# Power.net
KiCad netlist of a schematic drawn in Altium Designer
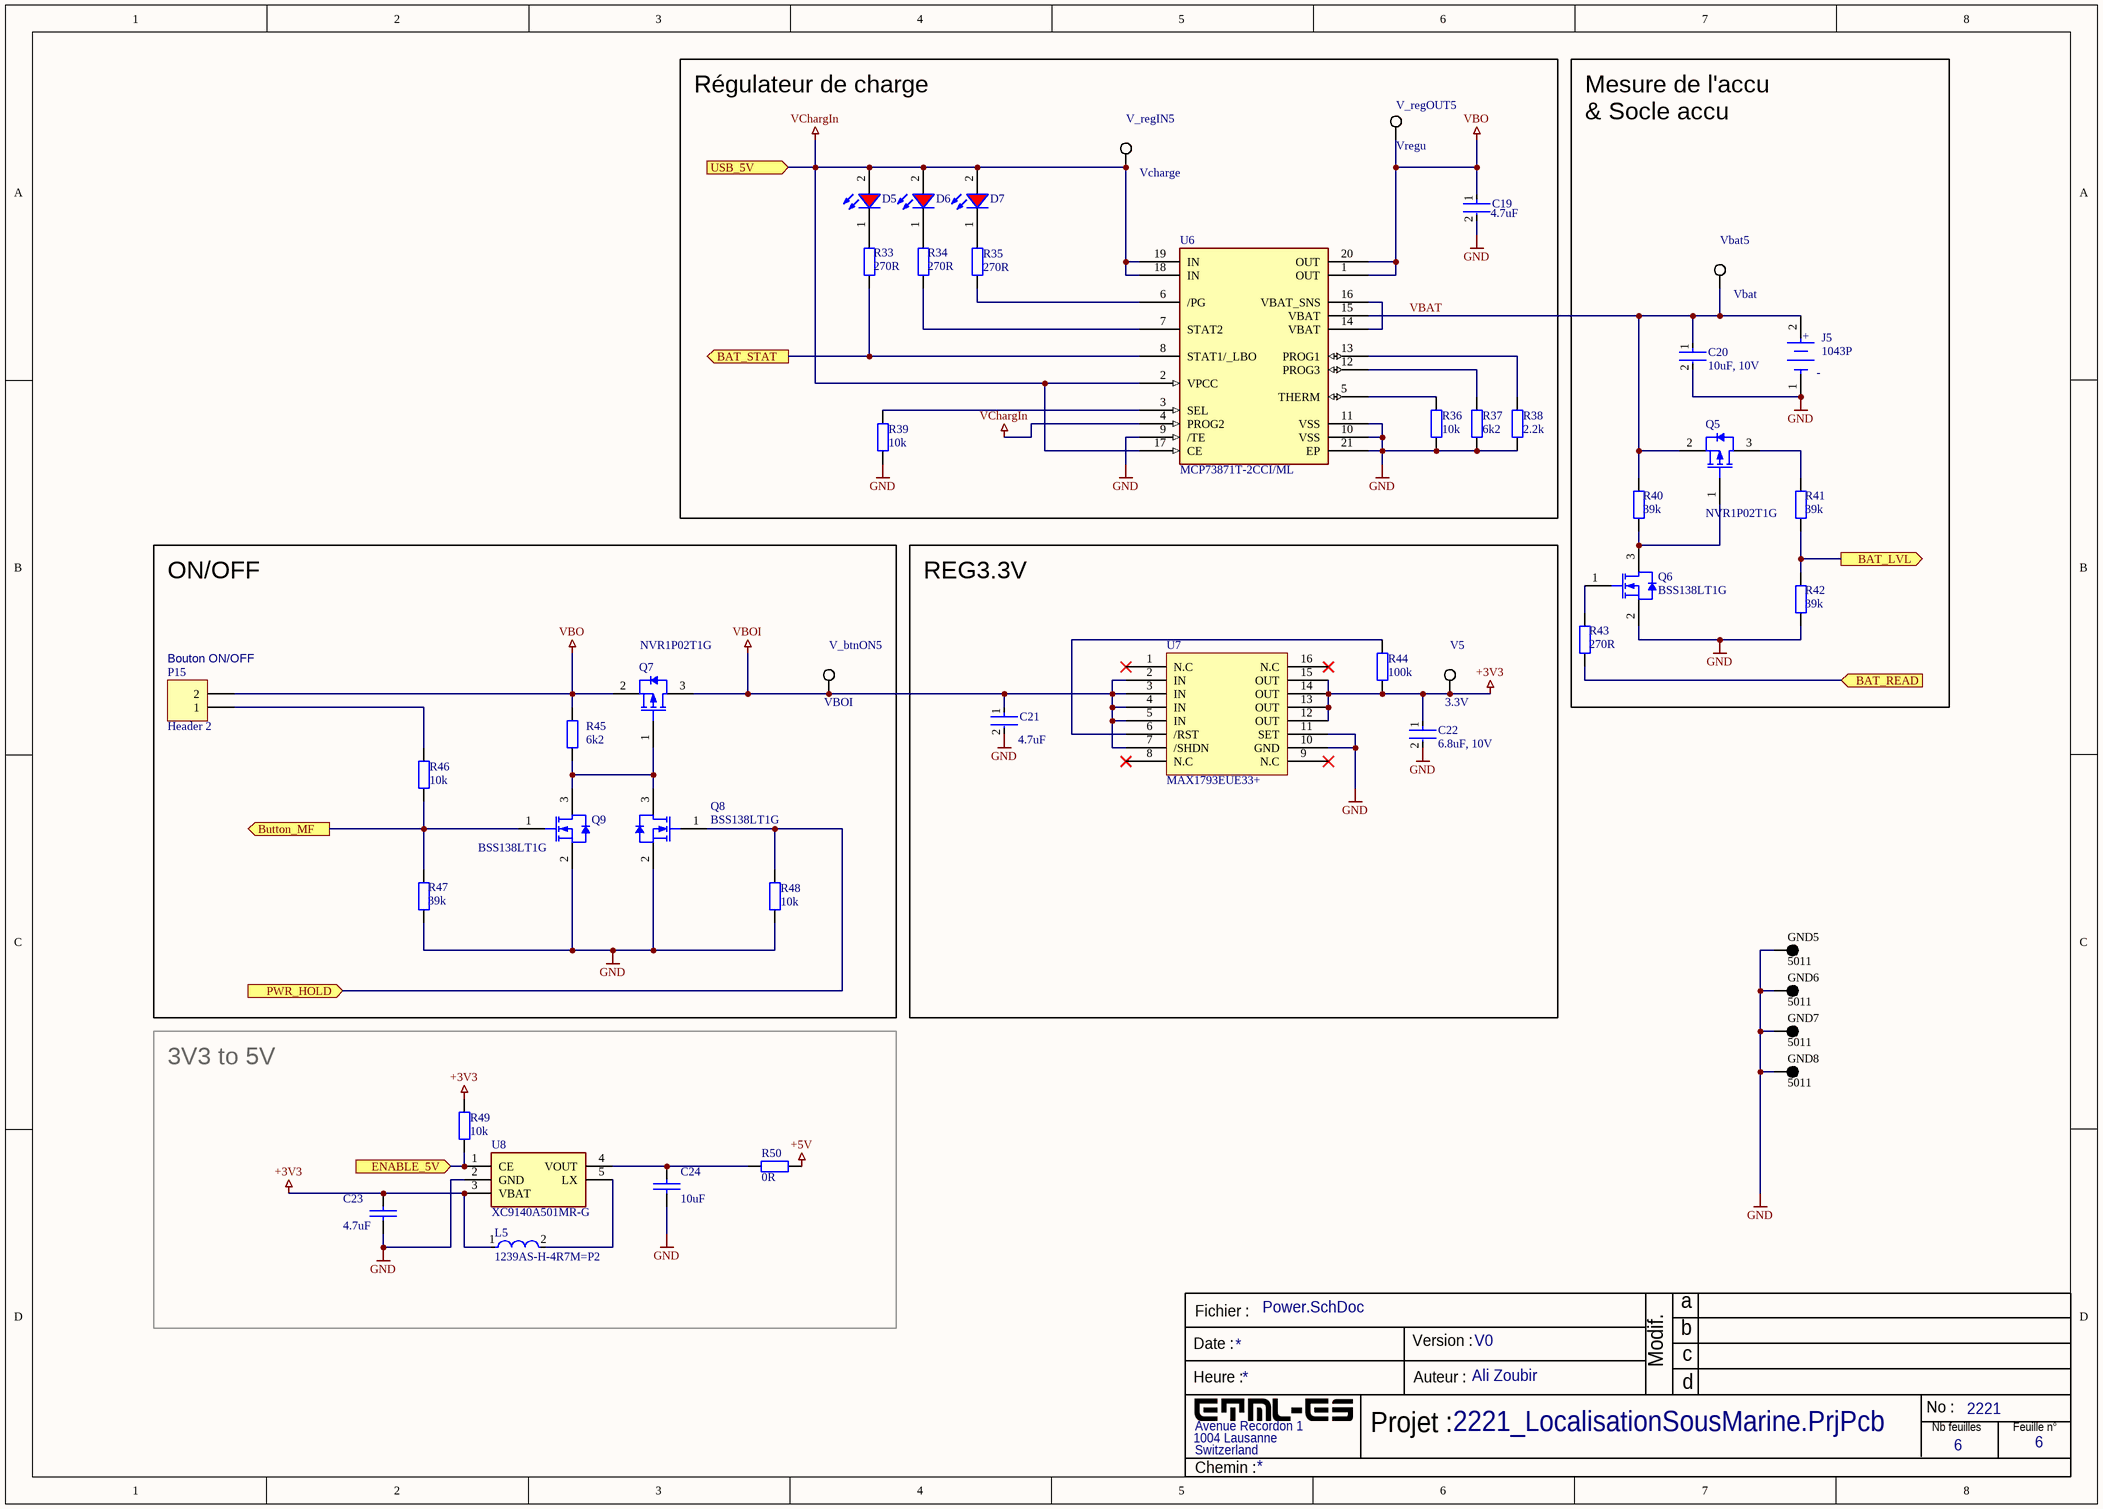
[diagram p0: Power.SchDoc]

(export (version "E")
  (design (tool "Eeschema 10.0.6"))
  (components
    (comp (ref "C19")
      (value "4.7uF, 35V")
      (footprint "6-0805_L")
      (description "Multilayer Ceramic Capacitors 4.7μF ±10% 35V X7R SMD 0805")
      (fields (field (name "TOLERANCE") "10%") (field (name "CAPACITANCE") "4.7uF"))
      (libsource (lib "2121_Robot3roues_V2.0") (part "b4654b650e69147ec39a6b967a45e02"))
    )
    (comp (ref "C20")
      (value "10uF, 10V")
      (footprint "6-0805_L")
      (description "CAP CER 10UF 10V X5R 0805")
      (fields (field (name "TOLERANCE") "10%") (field (name "MANUFACTURER PART NUMBER") "C0805C106K8PACTU"))
      (libsource (lib "2121_Robot3roues_V2.0") (part "11868f565c42a9108669ba33697ecf6"))
    )
    (comp (ref "C21")
      (value "4.7uF, 35V")
      (footprint "6-0805_L")
      (description "Multilayer Ceramic Capacitors 4.7μF ±10% 35V X7R SMD 0805")
      (fields (field (name "TOLERANCE") "10%") (field (name "CAPACITANCE") "4.7uF"))
      (libsource (lib "2121_Robot3roues_V2.0") (part "b4654b650e69147ec39a6b967a45e02"))
    )
    (comp (ref "C22")
      (value "6.8uF, 10V")
      (footprint "6-0805_L")
      (description "Cap Ceramic 6.8uF 10V X5R 20% Pad SMD 0805 +85°C Automotive T/R")
      (fields (field (name "TOLERANCE") "20%"))
      (libsource (lib "2121_Robot3roues_V2.0") (part "b4654b650e69147ec39a6b967a45e02"))
    )
    (comp (ref "C23") (value "4.7uF") (footprint "6-0805_L") (libsource (lib "*") (part "C")))
    (comp (ref "C24") (value "10uF") (footprint "6-0805_L") (libsource (lib "*") (part "C")))
    (comp (ref "D5")
      (value "Super Red, 1.9 V")
      (footprint "WL-SMCW_0805_150080xx75000")
      (description "SMT Mono-color Chip LED Waterclear WL-SMCW, size 0805, Super Red, 1.9 V, 140 deg, 60 mcd")
      (fields (field (name "PART NUMBER") "150080SS75000") (field (name "PUBLISHER") "Wurth Elektronik"))
      (libsource (lib "VPA_v2b") (part "150080SS75000"))
    )
    (comp (ref "D6")
      (value "Super Red, 1.9 V")
      (footprint "WL-SMCW_0805_150080xx75000")
      (description "SMT Mono-color Chip LED Waterclear WL-SMCW, size 0805, Super Red, 1.9 V, 140 deg, 60 mcd")
      (fields (field (name "PART NUMBER") "150080SS75000") (field (name "PUBLISHER") "Wurth Elektronik"))
      (libsource (lib "VPA_v2b") (part "150080SS75000"))
    )
    (comp (ref "D7")
      (value "Super Red, 1.9 V")
      (footprint "WL-SMCW_0805_150080xx75000")
      (description "SMT Mono-color Chip LED Waterclear WL-SMCW, size 0805, Super Red, 1.9 V, 140 deg, 60 mcd")
      (fields (field (name "PART NUMBER") "150080SS75000") (field (name "PUBLISHER") "Wurth Elektronik"))
      (libsource (lib "VPA_v2b") (part "150080SS75000"))
    )
    (comp (ref "GND5")
      (value "5011")
      (footprint "KSTN-5011_V")
      (description "Test Point, Black, Through Hole, RoHS, Bulk")
      (fields (field (name "MANUFACTURER") "Keystone"))
      (libsource (lib "Altium Content Vault") (part "TESTPOINT_BLACK"))
    )
    (comp (ref "GND6")
      (value "5011")
      (footprint "KSTN-5011_V")
      (description "Test Point, Black, Through Hole, RoHS, Bulk")
      (fields (field (name "MANUFACTURER") "Keystone"))
      (libsource (lib "Altium Content Vault") (part "TESTPOINT_BLACK"))
    )
    (comp (ref "GND7")
      (value "5011")
      (footprint "KSTN-5011_V")
      (description "Test Point, Black, Through Hole, RoHS, Bulk")
      (fields (field (name "MANUFACTURER") "Keystone"))
      (libsource (lib "Altium Content Vault") (part "TESTPOINT_BLACK"))
    )
    (comp (ref "GND8")
      (value "5011")
      (footprint "KSTN-5011_V")
      (description "Test Point, Black, Through Hole, RoHS, Bulk")
      (fields (field (name "MANUFACTURER") "Keystone"))
      (libsource (lib "Altium Content Vault") (part "TESTPOINT_BLACK"))
    )
    (comp (ref "J5")
      (value "1043P")
      (footprint "FP-1043P-MFG")
      (description "BATT HOLDER 18650 1 CELL PC PIN")
      (libsource (lib "Altium Content Vault") (part "60d3b5b901a8747834971d0eb8cf3fd"))
    )
    (comp (ref "L5")
      (value "1239AS-H-4R7M=P2")
      (footprint "FP-DFE252012C-IPC_B")
      (description "Shielded Wirewound Inductor 4.7uH 20% 1300mA 0.24Ω 1008 (2520)")
      (fields (field (name "TOLERANCE") "20%"))
      (libsource (lib "Altium Content Vault") (part "725321dda6339637d4d059423bc1c3c"))
    )
    (comp (ref "P15")
      (value "Header 2")
      (footprint "HDR1X2")
      (description "Header, 2-Pin")
      (fields (field (name "PUBLISHER") "Altium Limited"))
      (libsource (lib "Miscellaneous Connectors") (part "Header 2"))
    )
    (comp (ref "Q5")
      (value "NVR1P02T1G")
      (footprint "ONSC-SOT-23-3-318-08_V")
      (description "Power MOSFET, -20 V, -1 A, P-Channel, 3-Pin SOT-23, Pb-Free, Tape and Reel")
      (fields (field (name "MANUFACTURER") "On Semiconductor"))
      (libsource (lib "Altium Content Vault") (part "ONSC-PMOS-G1S2D3-3_D"))
    )
    (comp (ref "Q6")
      (value "BSS138LT1G")
      (footprint "ONSC-SOT-23-3-318-08_V")
      (description "Power MOSFET, 200 mA, 50 V, N-Channel, 3-Pin SOT-23, Pb-Free, Tape and Reel")
      (fields (field (name "MANUFACTURER") "On Semiconductor"))
      (libsource (lib "Altium Content Vault") (part "ONSC-NMOS-G1S2D3-3"))
    )
    (comp (ref "Q7")
      (value "NVR1P02T1G")
      (footprint "ONSC-SOT-23-3-318-08_V")
      (description "Power MOSFET, -20 V, -1 A, P-Channel, 3-Pin SOT-23, Pb-Free, Tape and Reel")
      (fields (field (name "MANUFACTURER") "On Semiconductor"))
      (libsource (lib "Altium Content Vault") (part "ONSC-PMOS-G1S2D3-3_D"))
    )
    (comp (ref "Q8")
      (value "BSS138LT1G")
      (footprint "ONSC-SOT-23-3-318-08_V")
      (description "Power MOSFET, 200 mA, 50 V, N-Channel, 3-Pin SOT-23, Pb-Free, Tape and Reel")
      (fields (field (name "MANUFACTURER") "On Semiconductor"))
      (libsource (lib "Altium Content Vault") (part "ONSC-NMOS-G1S2D3-3"))
    )
    (comp (ref "Q9")
      (value "BSS138LT1G")
      (footprint "ONSC-SOT-23-3-318-08_V")
      (description "Power MOSFET, 200 mA, 50 V, N-Channel, 3-Pin SOT-23, Pb-Free, Tape and Reel")
      (fields (field (name "MANUFACTURER") "On Semiconductor"))
      (libsource (lib "Altium Content Vault") (part "ONSC-NMOS-G1S2D3-3"))
    )
    (comp (ref "R33")
      (value "270R")
      (footprint "6-0805_L")
      (description "Res 0805")
      (fields (field (name "PART NUMBER") "ERJ6ENF2703V") (field (name "MANUFACTURER") "Panasonic"))
      (libsource (lib "2121_Robot3roues_V2.0") (part "RES"))
    )
    (comp (ref "R34")
      (value "270R")
      (footprint "6-0805_L")
      (description "Res 0805")
      (fields (field (name "PART NUMBER") "ERJ6ENF2703V") (field (name "MANUFACTURER") "Panasonic"))
      (libsource (lib "2121_Robot3roues_V2.0") (part "RES"))
    )
    (comp (ref "R35")
      (value "270R")
      (footprint "6-0805_L")
      (description "Res 0805")
      (fields (field (name "PART NUMBER") "ERJ6ENF2703V") (field (name "MANUFACTURER") "Panasonic"))
      (libsource (lib "") (part "RES_1"))
    )
    (comp (ref "R36")
      (value "10k")
      (footprint "6-0805_L")
      (description "Res 0805")
      (fields (field (name "MANUFACTURER") "Panasonic") (field (name "PART NUMBER") "ERJ-6ENF1002V"))
      (libsource (lib "2121_Robot3roues_V2.0") (part "RES"))
    )
    (comp (ref "R37")
      (value "6k2")
      (footprint "6-0805_L")
      (description "Res 0805")
      (fields (field (name "MANUFACTURER") "Vishay Dale") (field (name "PART NUMBER") "CRCW08055K60JNEA"))
      (libsource (lib "2121_Robot3roues_V2.0") (part "RES"))
    )
    (comp (ref "R38")
      (value "2.2k")
      (footprint "6-0805_L")
      (description "Res 0805")
      (fields (field (name "PART NUMBER") "CRCW08051K00FKEA") (field (name "MANUFACTURER") "Vishay Dale"))
      (libsource (lib "2121_Robot3roues_V2.0") (part "RES"))
    )
    (comp (ref "R39")
      (value "10k")
      (footprint "6-0805_L")
      (description "Res 0805")
      (fields (field (name "MANUFACTURER") "Panasonic") (field (name "PART NUMBER") "ERJ-6ENF1002V"))
      (libsource (lib "2121_Robot3roues_V2.0") (part "RES"))
    )
    (comp (ref "R40")
      (value "39k")
      (footprint "6-0805_L")
      (description "Res 0805")
      (fields (field (name "PART NUMBER") "ERJ-6GEYJ393V") (field (name "MANUFACTURER") "Panasonic"))
      (libsource (lib "2121_Robot3roues_V2.0") (part "RES"))
    )
    (comp (ref "R41")
      (value "39k")
      (footprint "6-0805_L")
      (description "Res 0805")
      (fields (field (name "PART NUMBER") "ERJ-6GEYJ393V") (field (name "MANUFACTURER") "Panasonic"))
      (libsource (lib "2121_Robot3roues_V2.0") (part "RES"))
    )
    (comp (ref "R42")
      (value "39k")
      (footprint "6-0805_L")
      (description "Res 0805")
      (fields (field (name "PART NUMBER") "ERJ-6GEYJ393V") (field (name "MANUFACTURER") "Panasonic"))
      (libsource (lib "2121_Robot3roues_V2.0") (part "RES"))
    )
    (comp (ref "R43")
      (value "270R")
      (footprint "6-0805_L")
      (description "Res 0805")
      (fields (field (name "PART NUMBER") "ERJ6ENF2703V") (field (name "MANUFACTURER") "Panasonic"))
      (libsource (lib "2121_Robot3roues_V2.0") (part "RES"))
    )
    (comp (ref "R44")
      (value "100k")
      (footprint "6-0805_L")
      (description "Res 0805")
      (fields (field (name "MANUFACTURER") "Panasonic") (field (name "PART NUMBER") "ERJ-P06J104V"))
      (libsource (lib "2121_Robot3roues_V2.0") (part "RES"))
    )
    (comp (ref "R45")
      (value "6k2")
      (footprint "6-0805_L")
      (description "Res 0805")
      (fields (field (name "PART NUMBER") "ERJ6ENF6201V") (field (name "MANUFACTURER") "Panasonic"))
      (libsource (lib "2121_Robot3roues_V2.0") (part "RES"))
    )
    (comp (ref "R46")
      (value "10k")
      (footprint "6-0805_L")
      (description "Res 0805")
      (fields (field (name "MANUFACTURER") "Panasonic") (field (name "PART NUMBER") "ERJ-6ENF1002V"))
      (libsource (lib "2121_Robot3roues_V2.0") (part "RES"))
    )
    (comp (ref "R47")
      (value "39k")
      (footprint "6-0805_L")
      (description "Res 0805")
      (fields (field (name "PART NUMBER") "ERJ-6GEYJ393V") (field (name "MANUFACTURER") "Panasonic"))
      (libsource (lib "2121_Robot3roues_V2.0") (part "RES"))
    )
    (comp (ref "R48")
      (value "10k")
      (footprint "6-0805_L")
      (description "Res 0805")
      (fields (field (name "MANUFACTURER") "Panasonic") (field (name "PART NUMBER") "ERJ-6ENF1002V"))
      (libsource (lib "2121_Robot3roues_V2.0") (part "RES"))
    )
    (comp (ref "R49")
      (value "10k")
      (footprint "6-0805_L")
      (description "Res 0805")
      (fields (field (name "MANUFACTURER") "Panasonic") (field (name "PART NUMBER") "ERJ-6ENF1002V"))
      (libsource (lib "2121_Robot3roues_V2.0") (part "RES"))
    )
    (comp (ref "R50")
      (value "0R")
      (footprint "6-0805_L")
      (description "Res 0805")
      (fields (field (name "PUBLISHER") "Altium Limited"))
      (libsource (lib "Miscellaneous Devices") (part "Res2"))
    )
    (comp (ref "U6")
      (value "MCP73871T-2CCI/ML")
      (footprint "Microchip_C04-126_IPC_B")
      (description "Charger IC Lithium Ion/Polymer 20-QFN _4x4_")
      (fields (field (name "MF") "Microchip") (field (name "DIGI-KEY_PART_NUMBER") "MCP73871T-2CCI/MLCT-ND"))
      (libsource (lib "2221-LIB") (part "MCP73871T-2CCI/ML"))
    )
    (comp (ref "U7")
      (value "MAX1793EUE33+")
      (footprint "TSOP65P640X110_HS-17N")
      (libsource (lib "2221-LIB") (part "MAX1793EUE33+"))
    )
    (comp (ref "U8")
      (value "XC9140A501MR-G")
      (footprint "SOT95P280X130-5N")
      (description "Switching Voltage Regulators PFM Control Snchrns StepUpDCDC Converter")
      (fields (field (name "MOUSER PART NUMBER") "865-XC9140A501MR-G"))
      (libsource (lib "2221-LIB") (part "XC9140A501MR-G"))
    )
    (comp (ref "V5")
      (value "3.3V")
      (footprint "KSTN-5019_V")
      (description "Test Point, 1 Position SMD, RoHS, Tape and Reel")
      (libsource (lib "Altium Content Vault") (part "TESTPOINT_WHITE"))
    )
    (comp (ref "Vbat5")
      (value "Vbat")
      (footprint "KSTN-5019_V")
      (description "Test Point, 1 Position SMD, RoHS, Tape and Reel")
      (libsource (lib "Altium Content Vault") (part "TESTPOINT_WHITE"))
    )
    (comp (ref "V_btnON5")
      (value "VBOI")
      (footprint "KSTN-5019_V")
      (description "Test Point, 1 Position SMD, RoHS, Tape and Reel")
      (libsource (lib "Altium Content Vault") (part "TESTPOINT_WHITE"))
    )
    (comp (ref "V_regIN5")
      (value "Vcharge")
      (footprint "KSTN-5019_V")
      (description "Test Point, 1 Position SMD, RoHS, Tape and Reel")
      (libsource (lib "Altium Content Vault") (part "TESTPOINT_WHITE"))
    )
    (comp (ref "V_regOUT5")
      (value "Vregu")
      (footprint "KSTN-5019_V")
      (description "Test Point, 1 Position SMD, RoHS, Tape and Reel")
      (libsource (lib "Altium Content Vault") (part "TESTPOINT_WHITE"))
    )
  )
  (nets
    (net (code "1") (name "+3V3") (class "Default")
      (node (ref "C22") (pin "1") (pinfunction "1_1") (pintype "passive"))
      (node (ref "C23") (pin "1") (pinfunction "1_1") (pintype "passive"))
      (node (ref "L5") (pin "1") (pinfunction "1_1") (pintype "passive"))
      (node (ref "R44") (pin "1") (pinfunction "1_1") (pintype "passive"))
      (node (ref "R49") (pin "2") (pinfunction "2_2") (pintype "passive"))
      (node (ref "U7") (pin "12") (pinfunction "OUT_12") (pintype "passive"))
      (node (ref "U7") (pin "13") (pinfunction "OUT_13") (pintype "passive"))
      (node (ref "U7") (pin "14") (pinfunction "OUT_14") (pintype "passive"))
      (node (ref "U7") (pin "15") (pinfunction "OUT_15") (pintype "passive"))
      (node (ref "U8") (pin "3") (pinfunction "VBAT_3") (pintype "passive"))
      (node (ref "V5") (pin "1") (pinfunction "1_1") (pintype "passive"))
    )
    (net (code "2") (name "+5V") (class "Default")
      (node (ref "R50") (pin "1") (pinfunction "1_1") (pintype "passive"))
    )
    (net (code "3") (name "/BAT_LVL") (class "Default")
      (node (ref "R41") (pin "1") (pinfunction "1_1") (pintype "passive"))
      (node (ref "R42") (pin "2") (pinfunction "2_2") (pintype "passive"))
    )
    (net (code "4") (name "/BAT_READ") (class "Default")
      (node (ref "R43") (pin "1") (pinfunction "1_1") (pintype "passive"))
    )
    (net (code "5") (name "/BAT_STAT") (class "Default")
      (node (ref "R33") (pin "1") (pinfunction "1_1") (pintype "passive"))
      (node (ref "U6") (pin "8") (pinfunction "STAT1/_LBO_8") (pintype "passive"))
    )
    (net (code "6") (name "/Button_MF") (class "Default")
      (node (ref "Q9") (pin "1") (pinfunction "G_1") (pintype "passive"))
      (node (ref "R46") (pin "1") (pinfunction "1_1") (pintype "passive"))
      (node (ref "R47") (pin "2") (pinfunction "2_2") (pintype "passive"))
    )
    (net (code "7") (name "/ENABLE_5V") (class "Default")
      (node (ref "R49") (pin "1") (pinfunction "1_1") (pintype "passive"))
      (node (ref "U8") (pin "1") (pinfunction "CE_1") (pintype "passive"))
    )
    (net (code "8") (name "/PWR_HOLD") (class "Default")
      (node (ref "Q8") (pin "1") (pinfunction "G_1") (pintype "passive"))
      (node (ref "R48") (pin "2") (pinfunction "2_2") (pintype "passive"))
    )
    (net (code "9") (name "/VBAT") (class "Default")
      (node (ref "C20") (pin "1") (pinfunction "1_1") (pintype "passive"))
      (node (ref "J5") (pin "2") (pinfunction "A_2") (pintype "passive"))
      (node (ref "Q5") (pin "2") (pinfunction "S_2") (pintype "passive"))
      (node (ref "R40") (pin "2") (pinfunction "2_2") (pintype "passive"))
      (node (ref "U6") (pin "15") (pinfunction "VBAT_15") (pintype "passive"))
      (node (ref "Vbat5") (pin "1") (pinfunction "1_1") (pintype "passive"))
    )
    (net (code "10") (name "GND") (class "Default")
      (node (ref "C19") (pin "2") (pinfunction "2_2") (pintype "passive"))
      (node (ref "C20") (pin "2") (pinfunction "2_2") (pintype "passive"))
      (node (ref "C21") (pin "2") (pinfunction "2_2") (pintype "passive"))
      (node (ref "C22") (pin "2") (pinfunction "2_2") (pintype "passive"))
      (node (ref "C23") (pin "2") (pinfunction "2_2") (pintype "passive"))
      (node (ref "C24") (pin "2") (pinfunction "2_2") (pintype "passive"))
      (node (ref "GND5") (pin "1") (pinfunction "1_1") (pintype "passive"))
      (node (ref "GND6") (pin "1") (pinfunction "1_1") (pintype "passive"))
      (node (ref "GND7") (pin "1") (pinfunction "1_1") (pintype "passive"))
      (node (ref "GND8") (pin "1") (pinfunction "1_1") (pintype "passive"))
      (node (ref "J5") (pin "1") (pinfunction "C_1") (pintype "passive"))
      (node (ref "Q6") (pin "2") (pinfunction "S_2") (pintype "passive"))
      (node (ref "Q8") (pin "2") (pinfunction "S_2") (pintype "passive"))
      (node (ref "Q9") (pin "2") (pinfunction "S_2") (pintype "passive"))
      (node (ref "R36") (pin "1") (pinfunction "1_1") (pintype "passive"))
      (node (ref "R37") (pin "1") (pinfunction "1_1") (pintype "passive"))
      (node (ref "R38") (pin "1") (pinfunction "1_1") (pintype "passive"))
      (node (ref "R39") (pin "1") (pinfunction "1_1") (pintype "passive"))
      (node (ref "R42") (pin "1") (pinfunction "1_1") (pintype "passive"))
      (node (ref "R47") (pin "1") (pinfunction "1_1") (pintype "passive"))
      (node (ref "R48") (pin "1") (pinfunction "1_1") (pintype "passive"))
      (node (ref "U6") (pin "10") (pinfunction "VSS_10") (pintype "passive"))
      (node (ref "U6") (pin "11") (pinfunction "VSS_11") (pintype "passive"))
      (node (ref "U6") (pin "21") (pinfunction "EP_21") (pintype "passive"))
      (node (ref "U6") (pin "9") (pinfunction "/TE_9") (pintype "input"))
      (node (ref "U7") (pin "10") (pinfunction "GND_10") (pintype "passive"))
      (node (ref "U7") (pin "11") (pinfunction "SET_11") (pintype "passive"))
      (node (ref "U8") (pin "2") (pinfunction "GND_2") (pintype "passive"))
    )
    (net (code "11") (name "Net-(D5-K)") (class "Default")
      (node (ref "D5") (pin "1") (pinfunction "K_1") (pintype "passive"))
      (node (ref "R33") (pin "2") (pinfunction "2_2") (pintype "passive"))
    )
    (net (code "12") (name "Net-(D6-K)") (class "Default")
      (node (ref "D6") (pin "1") (pinfunction "K_1") (pintype "passive"))
      (node (ref "R34") (pin "2") (pinfunction "2_2") (pintype "passive"))
    )
    (net (code "13") (name "Net-(D7-K)") (class "Default")
      (node (ref "D7") (pin "1") (pinfunction "K_1") (pintype "passive"))
      (node (ref "R35") (pin "1") (pinfunction "1_1") (pintype "passive"))
    )
    (net (code "14") (name "Net-(P15-Pad1)") (class "Default")
      (node (ref "P15") (pin "1") (pinfunction "1_1") (pintype "passive"))
      (node (ref "R46") (pin "2") (pinfunction "2_2") (pintype "passive"))
    )
    (net (code "15") (name "Net-(Q5-D)") (class "Default")
      (node (ref "Q5") (pin "3") (pinfunction "D_3") (pintype "passive"))
      (node (ref "R41") (pin "2") (pinfunction "2_2") (pintype "passive"))
    )
    (net (code "16") (name "Net-(Q5-G)") (class "Default")
      (node (ref "Q5") (pin "1") (pinfunction "G_1") (pintype "passive"))
      (node (ref "Q6") (pin "3") (pinfunction "D_3") (pintype "passive"))
      (node (ref "R40") (pin "1") (pinfunction "1_1") (pintype "passive"))
    )
    (net (code "17") (name "Net-(Q6-G)") (class "Default")
      (node (ref "Q6") (pin "1") (pinfunction "G_1") (pintype "passive"))
      (node (ref "R43") (pin "2") (pinfunction "2_2") (pintype "passive"))
    )
    (net (code "18") (name "Net-(Q7-G)") (class "Default")
      (node (ref "Q7") (pin "1") (pinfunction "G_1") (pintype "passive"))
      (node (ref "Q8") (pin "3") (pinfunction "D_3") (pintype "passive"))
      (node (ref "Q9") (pin "3") (pinfunction "D_3") (pintype "passive"))
      (node (ref "R45") (pin "1") (pinfunction "1_1") (pintype "passive"))
    )
    (net (code "19") (name "Net-(U6-PROG1)") (class "Default")
      (node (ref "R38") (pin "2") (pinfunction "2_2") (pintype "passive"))
      (node (ref "U6") (pin "13") (pinfunction "PROG1_13") (pintype "bidirectional"))
    )
    (net (code "20") (name "Net-(U6-PROG3)") (class "Default")
      (node (ref "R37") (pin "2") (pinfunction "2_2") (pintype "passive"))
      (node (ref "U6") (pin "12") (pinfunction "PROG3_12") (pintype "bidirectional"))
    )
    (net (code "21") (name "Net-(U6-SEL)") (class "Default")
      (node (ref "R39") (pin "2") (pinfunction "2_2") (pintype "passive"))
      (node (ref "U6") (pin "3") (pinfunction "SEL_3") (pintype "input"))
    )
    (net (code "22") (name "Net-(U6-STAT2)") (class "Default")
      (node (ref "R34") (pin "1") (pinfunction "1_1") (pintype "passive"))
      (node (ref "U6") (pin "7") (pinfunction "STAT2_7") (pintype "passive"))
    )
    (net (code "23") (name "Net-(U6-THERM)") (class "Default")
      (node (ref "R36") (pin "2") (pinfunction "2_2") (pintype "passive"))
      (node (ref "U6") (pin "5") (pinfunction "THERM_5") (pintype "bidirectional"))
    )
    (net (code "24") (name "Net-(U6-VBAT_SNS)") (class "Default")
      (node (ref "U6") (pin "14") (pinfunction "VBAT_14") (pintype "passive"))
      (node (ref "U6") (pin "16") (pinfunction "VBAT_SNS_16") (pintype "passive"))
    )
    (net (code "25") (name "Net-(U6-{slash}PG)") (class "Default")
      (node (ref "R35") (pin "2") (pinfunction "2_2") (pintype "passive"))
      (node (ref "U6") (pin "6") (pinfunction "/PG_6") (pintype "passive"))
    )
    (net (code "26") (name "Net-(U7-{slash}RST)") (class "Default")
      (node (ref "R44") (pin "2") (pinfunction "2_2") (pintype "passive"))
      (node (ref "U7") (pin "6") (pinfunction "/RST_6") (pintype "passive"))
    )
    (net (code "27") (name "Net-(U8-LX)") (class "Default")
      (node (ref "L5") (pin "2") (pinfunction "2_2") (pintype "passive"))
      (node (ref "U8") (pin "5") (pinfunction "LX_5") (pintype "passive"))
    )
    (net (code "28") (name "Net-(U8-VOUT)") (class "Default")
      (node (ref "C24") (pin "1") (pinfunction "1_1") (pintype "passive"))
      (node (ref "R50") (pin "2") (pinfunction "2_2") (pintype "passive"))
      (node (ref "U8") (pin "4") (pinfunction "VOUT_4") (pintype "passive"))
    )
    (net (code "29") (name "VBO") (class "Default")
      (node (ref "C19") (pin "1") (pinfunction "1_1") (pintype "passive"))
      (node (ref "P15") (pin "2") (pinfunction "2_2") (pintype "passive"))
      (node (ref "Q7") (pin "2") (pinfunction "S_2") (pintype "passive"))
      (node (ref "R45") (pin "2") (pinfunction "2_2") (pintype "passive"))
      (node (ref "U6") (pin "1") (pinfunction "OUT_1") (pintype "passive"))
      (node (ref "U6") (pin "20") (pinfunction "OUT_20") (pintype "passive"))
      (node (ref "V_regOUT5") (pin "1") (pinfunction "1_1") (pintype "passive"))
    )
    (net (code "30") (name "VBOI") (class "Default")
      (node (ref "C21") (pin "1") (pinfunction "1_1") (pintype "passive"))
      (node (ref "Q7") (pin "3") (pinfunction "D_3") (pintype "passive"))
      (node (ref "U7") (pin "2") (pinfunction "IN_2") (pintype "passive"))
      (node (ref "U7") (pin "3") (pinfunction "IN_3") (pintype "passive"))
      (node (ref "U7") (pin "4") (pinfunction "IN_4") (pintype "passive"))
      (node (ref "U7") (pin "5") (pinfunction "IN_5") (pintype "passive"))
      (node (ref "U7") (pin "7") (pinfunction "/SHDN_7") (pintype "passive"))
      (node (ref "V_btnON5") (pin "1") (pinfunction "1_1") (pintype "passive"))
    )
    (net (code "31") (name "VChargIn") (class "Default")
      (node (ref "D5") (pin "2") (pinfunction "A_2") (pintype "passive"))
      (node (ref "D6") (pin "2") (pinfunction "A_2") (pintype "passive"))
      (node (ref "D7") (pin "2") (pinfunction "A_2") (pintype "passive"))
      (node (ref "U6") (pin "17") (pinfunction "CE_17") (pintype "input"))
      (node (ref "U6") (pin "18") (pinfunction "IN_18") (pintype "passive"))
      (node (ref "U6") (pin "19") (pinfunction "IN_19") (pintype "passive"))
      (node (ref "U6") (pin "2") (pinfunction "VPCC_2") (pintype "input"))
      (node (ref "U6") (pin "4") (pinfunction "PROG2_4") (pintype "input"))
      (node (ref "V_regIN5") (pin "1") (pinfunction "1_1") (pintype "passive"))
    )
    (net (code "32") (name "unconnected-(U7-N.C-Pad1)") (class "Default")
      (node (ref "U7") (pin "1") (pinfunction "N.C_1") (pintype "passive+no_connect"))
    )
    (net (code "33") (name "unconnected-(U7-N.C-Pad8)") (class "Default")
      (node (ref "U7") (pin "8") (pinfunction "N.C_8") (pintype "passive+no_connect"))
    )
    (net (code "34") (name "unconnected-(U7-N.C-Pad9)") (class "Default")
      (node (ref "U7") (pin "9") (pinfunction "N.C_9") (pintype "passive+no_connect"))
    )
    (net (code "35") (name "unconnected-(U7-N.C-Pad16)") (class "Default")
      (node (ref "U7") (pin "16") (pinfunction "N.C_16") (pintype "passive+no_connect"))
    )
  )
)
